# 05_Ethernet_Interface.net
KiCad netlist of a schematic drawn in Altium Designer
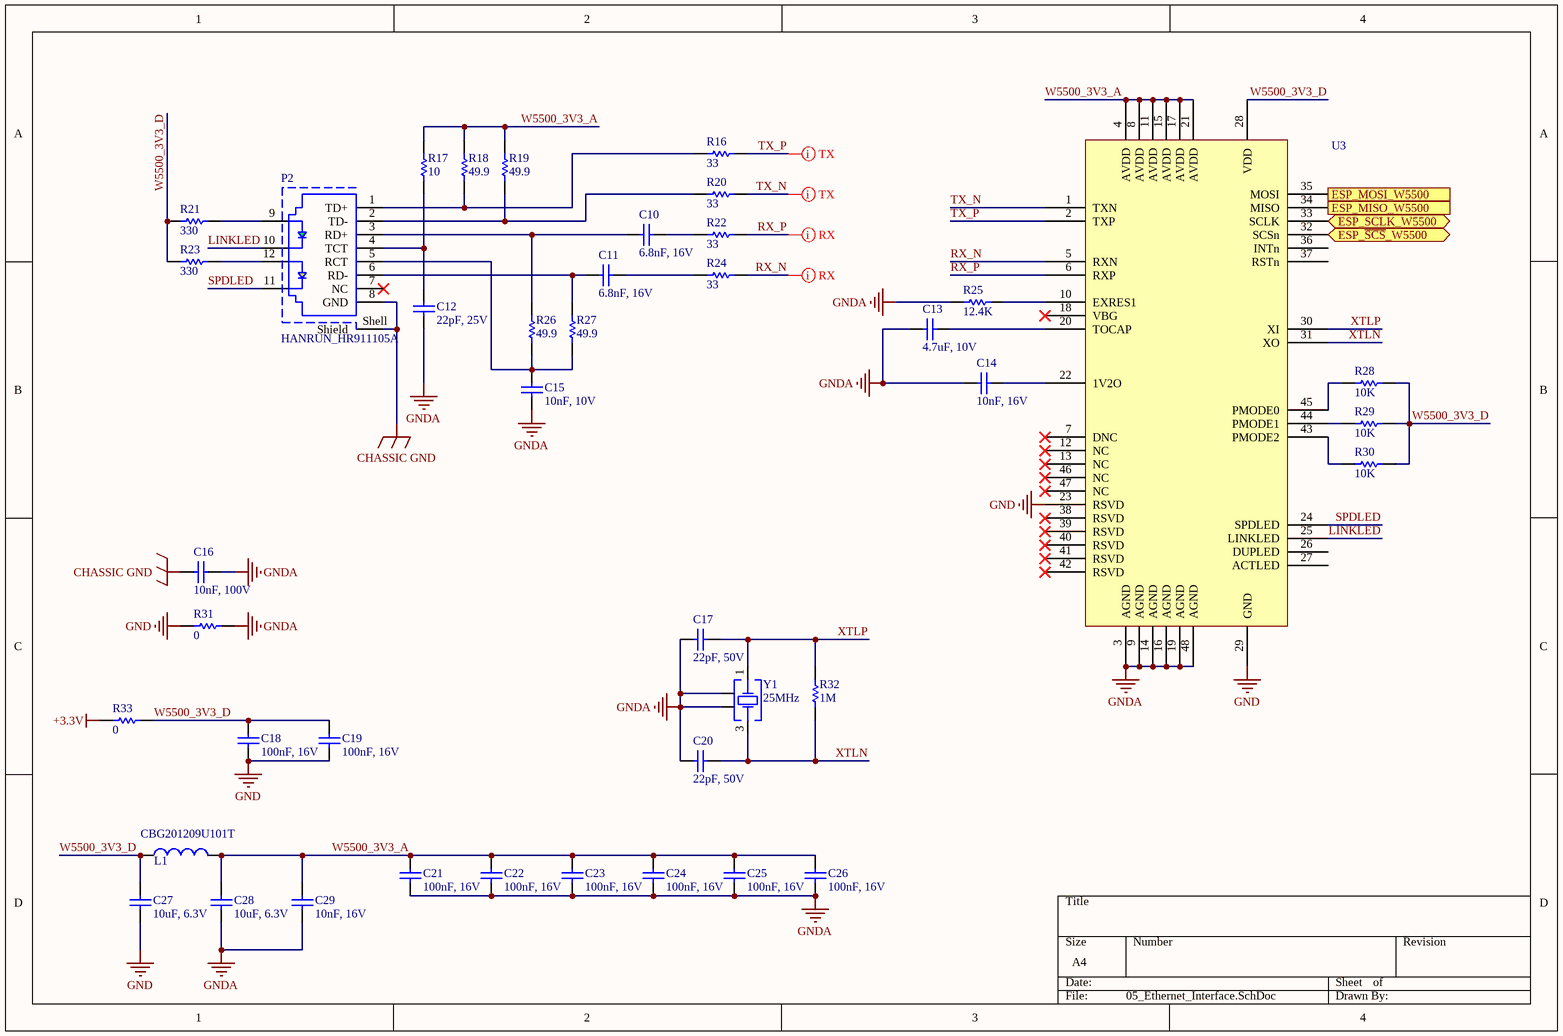
[diagram p0: 05_Ethernet_Interface.SchDoc]

(export (version "E")
  (design (tool "Eeschema 10.0.6"))
  (components
    (comp (ref "C10")
      (value "6.8nF, 16V")
      (footprint "WCAP-CSGP_0603_H=0.8mm_Reflow")
      (description "WCAP-CSGP Multilayer Ceramic Chip Capacitor, General Purpose, size 0603, X7R, 6.8nF, 16V")
      (fields
        (field (name "MANUFACTURER PART NUMBER") "885012206039")
        (field (name "MANUFACTURER") "Wurth Elektronik")
      )
      (libsource (lib "Altium_WCAP-CSGP (rev20a)") (part "885012206039"))
    )
    (comp (ref "C11")
      (value "6.8nF, 16V")
      (footprint "WCAP-CSGP_0603_H=0.8mm_Reflow")
      (description "WCAP-CSGP Multilayer Ceramic Chip Capacitor, General Purpose, size 0603, X7R, 6.8nF, 16V")
      (fields
        (field (name "MANUFACTURER PART NUMBER") "885012206039")
        (field (name "MANUFACTURER") "Wurth Elektronik")
      )
      (libsource (lib "Altium_WCAP-CSGP (rev20a)") (part "885012206039"))
    )
    (comp (ref "C12")
      (value "22pF, 25V")
      (footprint "WCAP-CSGP_0603_H=0.8mm_Reflow")
      (description "WCAP-CSGP Multilayer Ceramic Chip Capacitor, General Purpose, size 0603, NP0, 22pF, 25V")
      (fields
        (field (name "MANUFACTURER PART NUMBER") "885012006034")
        (field (name "MANUFACTURER") "Wurth Elektronik")
      )
      (libsource (lib "Altium_WCAP-CSGP (rev20a)") (part "885012006034"))
    )
    (comp (ref "C13")
      (value "4.7uF, 10V")
      (footprint "WCAP-CSGP_0603_H=0.8mm_Reflow")
      (description "WCAP-CSGP Multilayer Ceramic Chip Capacitor, General Purpose, size 0603, X5R, 4.7uF, 10V")
      (fields
        (field (name "MANUFACTURER PART NUMBER") "885012106012")
        (field (name "MANUFACTURER") "Wurth Elektronik")
      )
      (libsource (lib "Altium_WCAP-CSGP (rev20a)") (part "885012106012"))
    )
    (comp (ref "C14")
      (value "10nF, 16V")
      (footprint "WCAP-CSGP_0603_H=0.8mm_Reflow")
      (description "WCAP-CSGP Multilayer Ceramic Chip Capacitor, General Purpose, size 0603, X7R, 10nF, 16V")
      (fields
        (field (name "MANUFACTURER PART NUMBER") "885012206040")
        (field (name "MANUFACTURER") "Wurth Elektronik")
      )
      (libsource (lib "Altium_WCAP-CSGP (rev20a)") (part "885012206040"))
    )
    (comp (ref "C15")
      (value "10nF, 10V")
      (footprint "WCAP-CSGP_0603_H=0.8mm_Reflow")
      (description "WCAP-CSGP Multilayer Ceramic Chip Capacitor, General Purpose, size 0603, X7R, 10nF, 10V")
      (fields
        (field (name "MANUFACTURER PART NUMBER") "885012206014")
        (field (name "MANUFACTURER") "Wurth Elektronik")
      )
      (libsource (lib "Altium_WCAP-CSGP (rev20a)") (part "885012206014"))
    )
    (comp (ref "C16")
      (value "10nF, 100V")
      (footprint "WCAP-CSGP_0603_H=0.8mm_Reflow")
      (description "WCAP-CSGP Multilayer Ceramic Chip Capacitor, General Purpose, size 0603, X7R, 10nF, 100V")
      (fields
        (field (name "MANUFACTURER PART NUMBER") "885012206114")
        (field (name "MANUFACTURER") "Wurth Elektronik")
      )
      (libsource (lib "Altium_WCAP-CSGP (rev20a)") (part "885012206114"))
    )
    (comp (ref "C17")
      (value "22pF, 50V")
      (footprint "WCAP-CSGP_0603_H=0.8mm_Reflow")
      (description "WCAP-CSGP Multilayer Ceramic Chip Capacitor, General Purpose, size 0603, NP0, 22pF, 50V")
      (fields
        (field (name "MANUFACTURER PART NUMBER") "885012006053")
        (field (name "MANUFACTURER") "Wurth Elektronik")
      )
      (libsource (lib "Altium_WCAP-CSGP (rev20a)") (part "885012006053"))
    )
    (comp (ref "C18")
      (value "100nF, 16V")
      (footprint "WCAP-CSGP_0603_H=0.8mm_Reflow")
      (description "WCAP-CSGP Multilayer Ceramic Chip Capacitor, General Purpose, size 0603, X7R, 100nF, 16V")
      (fields
        (field (name "MANUFACTURER PART NUMBER") "885012206046")
        (field (name "MANUFACTURER") "Wurth Elektronik")
      )
      (libsource (lib "Altium_WCAP-CSGP (rev20a)") (part "885012206046"))
    )
    (comp (ref "C19")
      (value "100nF, 16V")
      (footprint "WCAP-CSGP_0603_H=0.8mm_Reflow")
      (description "WCAP-CSGP Multilayer Ceramic Chip Capacitor, General Purpose, size 0603, X7R, 100nF, 16V")
      (fields
        (field (name "MANUFACTURER PART NUMBER") "885012206046")
        (field (name "MANUFACTURER") "Wurth Elektronik")
      )
      (libsource (lib "Altium_WCAP-CSGP (rev20a)") (part "885012206046"))
    )
    (comp (ref "C20")
      (value "22pF, 50V")
      (footprint "WCAP-CSGP_0603_H=0.8mm_Reflow")
      (description "WCAP-CSGP Multilayer Ceramic Chip Capacitor, General Purpose, size 0603, NP0, 22pF, 50V")
      (fields
        (field (name "MANUFACTURER PART NUMBER") "885012006053")
        (field (name "MANUFACTURER") "Wurth Elektronik")
      )
      (libsource (lib "Altium_WCAP-CSGP (rev20a)") (part "885012006053"))
    )
    (comp (ref "C21")
      (value "100nF, 16V")
      (footprint "WCAP-CSGP_0603_H=0.8mm_Reflow")
      (description "WCAP-CSGP Multilayer Ceramic Chip Capacitor, General Purpose, size 0603, X7R, 100nF, 16V")
      (fields
        (field (name "MANUFACTURER PART NUMBER") "885012206046")
        (field (name "MANUFACTURER") "Wurth Elektronik")
      )
      (libsource (lib "Altium_WCAP-CSGP (rev20a)") (part "885012206046"))
    )
    (comp (ref "C22")
      (value "100nF, 16V")
      (footprint "WCAP-CSGP_0603_H=0.8mm_Reflow")
      (description "WCAP-CSGP Multilayer Ceramic Chip Capacitor, General Purpose, size 0603, X7R, 100nF, 16V")
      (fields
        (field (name "MANUFACTURER PART NUMBER") "885012206046")
        (field (name "MANUFACTURER") "Wurth Elektronik")
      )
      (libsource (lib "Altium_WCAP-CSGP (rev20a)") (part "885012206046"))
    )
    (comp (ref "C23")
      (value "100nF, 16V")
      (footprint "WCAP-CSGP_0603_H=0.8mm_Reflow")
      (description "WCAP-CSGP Multilayer Ceramic Chip Capacitor, General Purpose, size 0603, X7R, 100nF, 16V")
      (fields
        (field (name "MANUFACTURER PART NUMBER") "885012206046")
        (field (name "MANUFACTURER") "Wurth Elektronik")
      )
      (libsource (lib "Altium_WCAP-CSGP (rev20a)") (part "885012206046"))
    )
    (comp (ref "C24")
      (value "100nF, 16V")
      (footprint "WCAP-CSGP_0603_H=0.8mm_Reflow")
      (description "WCAP-CSGP Multilayer Ceramic Chip Capacitor, General Purpose, size 0603, X7R, 100nF, 16V")
      (fields
        (field (name "MANUFACTURER PART NUMBER") "885012206046")
        (field (name "MANUFACTURER") "Wurth Elektronik")
      )
      (libsource (lib "Altium_WCAP-CSGP (rev20a)") (part "885012206046"))
    )
    (comp (ref "C25")
      (value "100nF, 16V")
      (footprint "WCAP-CSGP_0603_H=0.8mm_Reflow")
      (description "WCAP-CSGP Multilayer Ceramic Chip Capacitor, General Purpose, size 0603, X7R, 100nF, 16V")
      (fields
        (field (name "MANUFACTURER PART NUMBER") "885012206046")
        (field (name "MANUFACTURER") "Wurth Elektronik")
      )
      (libsource (lib "Altium_WCAP-CSGP (rev20a)") (part "885012206046"))
    )
    (comp (ref "C26")
      (value "100nF, 16V")
      (footprint "WCAP-CSGP_0603_H=0.8mm_Reflow")
      (description "WCAP-CSGP Multilayer Ceramic Chip Capacitor, General Purpose, size 0603, X7R, 100nF, 16V")
      (fields
        (field (name "MANUFACTURER PART NUMBER") "885012206046")
        (field (name "MANUFACTURER") "Wurth Elektronik")
      )
      (libsource (lib "Altium_WCAP-CSGP (rev20a)") (part "885012206046"))
    )
    (comp (ref "C27")
      (value "10uF, 6.3V")
      (footprint "WCAP-CSGP_0603_H=0.8mm_Reflow")
      (description "WCAP-CSGP Multilayer Ceramic Chip Capacitor, General Purpose, size 0603, X5R, 10uF, 6.3V")
      (fields
        (field (name "MANUFACTURER PART NUMBER") "885012106006")
        (field (name "MANUFACTURER") "Wurth Elektronik")
      )
      (libsource (lib "Altium_WCAP-CSGP (rev20a)") (part "885012106006"))
    )
    (comp (ref "C28")
      (value "10uF, 6.3V")
      (footprint "WCAP-CSGP_0603_H=0.8mm_Reflow")
      (description "WCAP-CSGP Multilayer Ceramic Chip Capacitor, General Purpose, size 0603, X5R, 10uF, 6.3V")
      (fields
        (field (name "MANUFACTURER PART NUMBER") "885012106006")
        (field (name "MANUFACTURER") "Wurth Elektronik")
      )
      (libsource (lib "Altium_WCAP-CSGP (rev20a)") (part "885012106006"))
    )
    (comp (ref "C29")
      (value "10nF, 16V")
      (footprint "WCAP-CSGP_0603_H=0.8mm_Reflow")
      (description "WCAP-CSGP Multilayer Ceramic Chip Capacitor, General Purpose, size 0603, X7R, 10nF, 16V")
      (fields
        (field (name "MANUFACTURER PART NUMBER") "885012206040")
        (field (name "MANUFACTURER") "Wurth Elektronik")
      )
      (libsource (lib "Altium_WCAP-CSGP (rev20a)") (part "885012206040"))
    )
    (comp (ref "L1")
      (value "CBG201209U101T")
      (footprint "I0805")
      (libsource (lib "MiclsLib") (part "CBG201209U101T"))
    )
    (comp (ref "P2")
      (value "HANRUN_HR911105A")
      (footprint "HANRUN_HR911105A")
      (libsource (lib "MiclsLib") (part "HANRUN_HR911105A"))
    )
    (comp (ref "R16")
      (value "33")
      (footprint "R0603")
      (fields (field (name "Comment") "Resistor"))
      (libsource (lib "MiclsLib") (part "Resistor"))
    )
    (comp (ref "R17")
      (value "10")
      (footprint "R0603")
      (fields (field (name "Comment") "Resistor"))
      (libsource (lib "MiclsLib") (part "Resistor"))
    )
    (comp (ref "R18")
      (value "49.9")
      (footprint "R0603")
      (fields (field (name "Comment") "Resistor"))
      (libsource (lib "MiclsLib") (part "Resistor"))
    )
    (comp (ref "R19")
      (value "49.9")
      (footprint "R0603")
      (fields (field (name "Comment") "Resistor"))
      (libsource (lib "MiclsLib") (part "Resistor"))
    )
    (comp (ref "R20")
      (value "33")
      (footprint "R0603")
      (fields (field (name "Comment") "Resistor"))
      (libsource (lib "MiclsLib") (part "Resistor"))
    )
    (comp (ref "R21")
      (value "330")
      (footprint "R0603")
      (fields (field (name "Comment") "Resistor"))
      (libsource (lib "MiclsLib") (part "Resistor"))
    )
    (comp (ref "R22")
      (value "33")
      (footprint "R0603")
      (fields (field (name "Comment") "Resistor"))
      (libsource (lib "MiclsLib") (part "Resistor"))
    )
    (comp (ref "R23")
      (value "330")
      (footprint "R0603")
      (fields (field (name "Comment") "Resistor"))
      (libsource (lib "MiclsLib") (part "Resistor"))
    )
    (comp (ref "R24")
      (value "33")
      (footprint "R0603")
      (fields (field (name "Comment") "Resistor"))
      (libsource (lib "MiclsLib") (part "Resistor"))
    )
    (comp (ref "R25")
      (value "12.4K")
      (footprint "R0603")
      (fields (field (name "Comment") "Resistor"))
      (libsource (lib "MiclsLib") (part "Resistor"))
    )
    (comp (ref "R26")
      (value "49.9")
      (footprint "R0603")
      (fields (field (name "Comment") "Resistor"))
      (libsource (lib "MiclsLib") (part "Resistor"))
    )
    (comp (ref "R27")
      (value "49.9")
      (footprint "R0603")
      (fields (field (name "Comment") "Resistor"))
      (libsource (lib "MiclsLib") (part "Resistor"))
    )
    (comp (ref "R28")
      (value "10K")
      (footprint "R0603")
      (fields (field (name "Comment") "Resistor"))
      (libsource (lib "MiclsLib") (part "Resistor"))
    )
    (comp (ref "R29")
      (value "10K")
      (footprint "R0603")
      (fields (field (name "Comment") "Resistor"))
      (libsource (lib "MiclsLib") (part "Resistor"))
    )
    (comp (ref "R30")
      (value "10K")
      (footprint "R0603")
      (fields (field (name "Comment") "Resistor"))
      (libsource (lib "MiclsLib") (part "Resistor"))
    )
    (comp (ref "R31")
      (value "0")
      (footprint "R0603")
      (fields (field (name "Comment") "Resistor"))
      (libsource (lib "MiclsLib") (part "Resistor"))
    )
    (comp (ref "R32")
      (value "1M")
      (footprint "R0603")
      (fields (field (name "Comment") "Resistor"))
      (libsource (lib "MiclsLib") (part "Resistor"))
    )
    (comp (ref "R33")
      (value "0")
      (footprint "R0805")
      (fields (field (name "Comment") "Resistor"))
      (libsource (lib "MiclsLib") (part "Resistor"))
    )
    (comp (ref "U3")
      (value "W5500")
      (footprint "TSQFP50P900X900X160-48N")
      (libsource (lib "MiclsLib") (part "W5500"))
    )
    (comp (ref "Y1")
      (value "25MHz")
      (footprint "WE-XTAL_CFPX-180")
      (description "WE-XTAL Quartz Crystal, SMT, CFPX-180, 25MHz, +/-20ppm")
      (fields
        (field (name "MANUFACTURER PART NUMBER") "830108340809")
        (field (name "MANUFACTURER") "Wurth Elektronik")
      )
      (libsource (lib "Altium_WE-XTAL (rev20c)") (part "830108340809"))
    )
  )
  (nets
    (net (code "1") (name "+3.3V") (class "Default")
      (node (ref "R33") (pin "2") (pinfunction "2_2") (pintype "passive"))
    )
    (net (code "2") (name "/ESP_MISO_W5500") (class "Default")
      (node (ref "U3") (pin "34") (pinfunction "MISO_34") (pintype "passive"))
    )
    (net (code "3") (name "/ESP_MOSI_W5500") (class "Default")
      (node (ref "U3") (pin "35") (pinfunction "MOSI_35") (pintype "passive"))
    )
    (net (code "4") (name "/ESP_SCLK_W5500") (class "Default")
      (node (ref "U3") (pin "33") (pinfunction "SCLK_33") (pintype "passive"))
    )
    (net (code "5") (name "/ESP_~{SCS}_W5500") (class "Default")
      (node (ref "U3") (pin "32") (pinfunction "SCSn_32") (pintype "passive"))
    )
    (net (code "6") (name "/LINKLED") (class "Default")
      (node (ref "P2") (pin "10") (pinfunction "10_10") (pintype "passive"))
      (node (ref "U3") (pin "25") (pinfunction "LINKLED_25") (pintype "passive"))
    )
    (net (code "7") (name "/RX_N") (class "Default")
      (node (ref "R24") (pin "1") (pinfunction "1_1") (pintype "passive"))
      (node (ref "U3") (pin "5") (pinfunction "RXN_5") (pintype "passive"))
    )
    (net (code "8") (name "/RX_P") (class "Default")
      (node (ref "R22") (pin "1") (pinfunction "1_1") (pintype "passive"))
      (node (ref "U3") (pin "6") (pinfunction "RXP_6") (pintype "passive"))
    )
    (net (code "9") (name "/SPDLED") (class "Default")
      (node (ref "P2") (pin "11") (pinfunction "11_11") (pintype "passive"))
      (node (ref "U3") (pin "24") (pinfunction "SPDLED_24") (pintype "passive"))
    )
    (net (code "10") (name "/TX_N") (class "Default")
      (node (ref "R20") (pin "1") (pinfunction "1_1") (pintype "passive"))
      (node (ref "U3") (pin "1") (pinfunction "TXN_1") (pintype "passive"))
    )
    (net (code "11") (name "/TX_P") (class "Default")
      (node (ref "R16") (pin "1") (pinfunction "1_1") (pintype "passive"))
      (node (ref "U3") (pin "2") (pinfunction "TXP_2") (pintype "passive"))
    )
    (net (code "12") (name "/W5500_3V3_A") (class "Default")
      (node (ref "C21") (pin "2") (pinfunction "2_2") (pintype "passive"))
      (node (ref "C22") (pin "2") (pinfunction "2_2") (pintype "passive"))
      (node (ref "C23") (pin "2") (pinfunction "2_2") (pintype "passive"))
      (node (ref "C24") (pin "2") (pinfunction "2_2") (pintype "passive"))
      (node (ref "C25") (pin "2") (pinfunction "2_2") (pintype "passive"))
      (node (ref "C26") (pin "2") (pinfunction "2_2") (pintype "passive"))
      (node (ref "C28") (pin "2") (pinfunction "2_2") (pintype "passive"))
      (node (ref "C29") (pin "2") (pinfunction "2_2") (pintype "passive"))
      (node (ref "L1") (pin "2") (pinfunction "2_2") (pintype "passive"))
      (node (ref "R17") (pin "2") (pinfunction "2_2") (pintype "passive"))
      (node (ref "R18") (pin "2") (pinfunction "2_2") (pintype "passive"))
      (node (ref "R19") (pin "2") (pinfunction "2_2") (pintype "passive"))
      (node (ref "U3") (pin "11") (pinfunction "AVDD_11") (pintype "passive"))
      (node (ref "U3") (pin "15") (pinfunction "AVDD_15") (pintype "passive"))
      (node (ref "U3") (pin "17") (pinfunction "AVDD_17") (pintype "passive"))
      (node (ref "U3") (pin "21") (pinfunction "AVDD_21") (pintype "passive"))
      (node (ref "U3") (pin "4") (pinfunction "AVDD_4") (pintype "passive"))
      (node (ref "U3") (pin "8") (pinfunction "AVDD_8") (pintype "passive"))
    )
    (net (code "13") (name "/W5500_3V3_D") (class "Default")
      (node (ref "C18") (pin "2") (pinfunction "2_2") (pintype "passive"))
      (node (ref "C19") (pin "2") (pinfunction "2_2") (pintype "passive"))
      (node (ref "C27") (pin "2") (pinfunction "2_2") (pintype "passive"))
      (node (ref "L1") (pin "1") (pinfunction "1_1") (pintype "passive"))
      (node (ref "R21") (pin "2") (pinfunction "2_2") (pintype "passive"))
      (node (ref "R23") (pin "2") (pinfunction "2_2") (pintype "passive"))
      (node (ref "R28") (pin "2") (pinfunction "2_2") (pintype "passive"))
      (node (ref "R29") (pin "2") (pinfunction "2_2") (pintype "passive"))
      (node (ref "R30") (pin "2") (pinfunction "2_2") (pintype "passive"))
      (node (ref "R33") (pin "1") (pinfunction "1_1") (pintype "passive"))
      (node (ref "U3") (pin "28") (pinfunction "VDD_28") (pintype "passive"))
    )
    (net (code "14") (name "/XTLN") (class "Default")
      (node (ref "C20") (pin "2") (pinfunction "2_2") (pintype "passive"))
      (node (ref "R32") (pin "1") (pinfunction "1_1") (pintype "passive"))
      (node (ref "U3") (pin "31") (pinfunction "XO_31") (pintype "passive"))
      (node (ref "Y1") (pin "3") (pinfunction "Crystal_3") (pintype "passive"))
    )
    (net (code "15") (name "/XTLP") (class "Default")
      (node (ref "C17") (pin "2") (pinfunction "2_2") (pintype "passive"))
      (node (ref "R32") (pin "2") (pinfunction "2_2") (pintype "passive"))
      (node (ref "U3") (pin "30") (pinfunction "XI_30") (pintype "passive"))
      (node (ref "Y1") (pin "1") (pinfunction "Crystal_1") (pintype "passive"))
    )
    (net (code "16") (name "CHASSIC GND") (class "Default")
      (node (ref "C16") (pin "1") (pinfunction "1_1") (pintype "passive"))
      (node (ref "P2") (pin "8") (pinfunction "GND_8") (pintype "passive"))
      (node (ref "P2") (pin "Shell") (pinfunction "Shield_Shell") (pintype "passive"))
    )
    (net (code "17") (name "GND") (class "Default")
      (node (ref "C18") (pin "1") (pinfunction "1_1") (pintype "passive"))
      (node (ref "C19") (pin "1") (pinfunction "1_1") (pintype "passive"))
      (node (ref "C27") (pin "1") (pinfunction "1_1") (pintype "passive"))
      (node (ref "R31") (pin "2") (pinfunction "2_2") (pintype "passive"))
      (node (ref "U3") (pin "23") (pinfunction "RSVD_23") (pintype "passive"))
      (node (ref "U3") (pin "29") (pinfunction "GND_29") (pintype "passive"))
    )
    (net (code "18") (name "GNDA") (class "Default")
      (node (ref "C12") (pin "1") (pinfunction "1_1") (pintype "passive"))
      (node (ref "C13") (pin "1") (pinfunction "1_1") (pintype "passive"))
      (node (ref "C14") (pin "2") (pinfunction "2_2") (pintype "passive"))
      (node (ref "C15") (pin "1") (pinfunction "1_1") (pintype "passive"))
      (node (ref "C16") (pin "2") (pinfunction "2_2") (pintype "passive"))
      (node (ref "C17") (pin "1") (pinfunction "1_1") (pintype "passive"))
      (node (ref "C20") (pin "1") (pinfunction "1_1") (pintype "passive"))
      (node (ref "C21") (pin "1") (pinfunction "1_1") (pintype "passive"))
      (node (ref "C22") (pin "1") (pinfunction "1_1") (pintype "passive"))
      (node (ref "C23") (pin "1") (pinfunction "1_1") (pintype "passive"))
      (node (ref "C24") (pin "1") (pinfunction "1_1") (pintype "passive"))
      (node (ref "C25") (pin "1") (pinfunction "1_1") (pintype "passive"))
      (node (ref "C26") (pin "1") (pinfunction "1_1") (pintype "passive"))
      (node (ref "C28") (pin "1") (pinfunction "1_1") (pintype "passive"))
      (node (ref "C29") (pin "1") (pinfunction "1_1") (pintype "passive"))
      (node (ref "R25") (pin "2") (pinfunction "2_2") (pintype "passive"))
      (node (ref "R31") (pin "1") (pinfunction "1_1") (pintype "passive"))
      (node (ref "U3") (pin "14") (pinfunction "AGND_14") (pintype "passive"))
      (node (ref "U3") (pin "16") (pinfunction "AGND_16") (pintype "passive"))
      (node (ref "U3") (pin "19") (pinfunction "AGND_19") (pintype "passive"))
      (node (ref "U3") (pin "3") (pinfunction "AGND_3") (pintype "passive"))
      (node (ref "U3") (pin "48") (pinfunction "AGND_48") (pintype "passive"))
      (node (ref "U3") (pin "9") (pinfunction "AGND_9") (pintype "passive"))
      (node (ref "Y1") (pin "2") (pinfunction "GND&Lid_2") (pintype "passive"))
      (node (ref "Y1") (pin "4") (pinfunction "GND&Lid_4") (pintype "passive"))
    )
    (net (code "19") (name "Net-(C10-Pad2)") (class "Default")
      (node (ref "C10") (pin "2") (pinfunction "2_2") (pintype "passive"))
      (node (ref "R22") (pin "2") (pinfunction "2_2") (pintype "passive"))
    )
    (net (code "20") (name "Net-(C11-Pad2)") (class "Default")
      (node (ref "C11") (pin "2") (pinfunction "2_2") (pintype "passive"))
      (node (ref "R24") (pin "2") (pinfunction "2_2") (pintype "passive"))
    )
    (net (code "21") (name "Net-(P2-Pad9)") (class "Default")
      (node (ref "P2") (pin "9") (pinfunction "9_9") (pintype "passive"))
      (node (ref "R21") (pin "1") (pinfunction "1_1") (pintype "passive"))
    )
    (net (code "22") (name "Net-(P2-Pad12)") (class "Default")
      (node (ref "P2") (pin "12") (pinfunction "12_12") (pintype "passive"))
      (node (ref "R23") (pin "1") (pinfunction "1_1") (pintype "passive"))
    )
    (net (code "23") (name "Net-(P2-RCT)") (class "Default")
      (node (ref "C15") (pin "2") (pinfunction "2_2") (pintype "passive"))
      (node (ref "P2") (pin "5") (pinfunction "RCT_5") (pintype "passive"))
      (node (ref "R26") (pin "2") (pinfunction "2_2") (pintype "passive"))
      (node (ref "R27") (pin "2") (pinfunction "2_2") (pintype "passive"))
    )
    (net (code "24") (name "Net-(P2-RD+)") (class "Default")
      (node (ref "C10") (pin "1") (pinfunction "1_1") (pintype "passive"))
      (node (ref "P2") (pin "3") (pinfunction "RD+_3") (pintype "passive"))
      (node (ref "R26") (pin "1") (pinfunction "1_1") (pintype "passive"))
    )
    (net (code "25") (name "Net-(P2-RD-)") (class "Default")
      (node (ref "C11") (pin "1") (pinfunction "1_1") (pintype "passive"))
      (node (ref "P2") (pin "6") (pinfunction "RD-_6") (pintype "passive"))
      (node (ref "R27") (pin "1") (pinfunction "1_1") (pintype "passive"))
    )
    (net (code "26") (name "Net-(P2-TCT)") (class "Default")
      (node (ref "C12") (pin "2") (pinfunction "2_2") (pintype "passive"))
      (node (ref "P2") (pin "4") (pinfunction "TCT_4") (pintype "passive"))
      (node (ref "R17") (pin "1") (pinfunction "1_1") (pintype "passive"))
    )
    (net (code "27") (name "Net-(P2-TD+)") (class "Default")
      (node (ref "P2") (pin "1") (pinfunction "TD+_1") (pintype "passive"))
      (node (ref "R16") (pin "2") (pinfunction "2_2") (pintype "passive"))
      (node (ref "R18") (pin "1") (pinfunction "1_1") (pintype "passive"))
    )
    (net (code "28") (name "Net-(P2-TD-)") (class "Default")
      (node (ref "P2") (pin "2") (pinfunction "TD-_2") (pintype "passive"))
      (node (ref "R19") (pin "1") (pinfunction "1_1") (pintype "passive"))
      (node (ref "R20") (pin "2") (pinfunction "2_2") (pintype "passive"))
    )
    (net (code "29") (name "Net-(U3-1V2O)") (class "Default")
      (node (ref "C14") (pin "1") (pinfunction "1_1") (pintype "passive"))
      (node (ref "U3") (pin "22") (pinfunction "1V2O_22") (pintype "passive"))
    )
    (net (code "30") (name "Net-(U3-EXRES1)") (class "Default")
      (node (ref "R25") (pin "1") (pinfunction "1_1") (pintype "passive"))
      (node (ref "U3") (pin "10") (pinfunction "EXRES1_10") (pintype "passive"))
    )
    (net (code "31") (name "Net-(U3-PMODE0)") (class "Default")
      (node (ref "R28") (pin "1") (pinfunction "1_1") (pintype "passive"))
      (node (ref "U3") (pin "45") (pinfunction "PMODE0_45") (pintype "passive"))
    )
    (net (code "32") (name "Net-(U3-PMODE1)") (class "Default")
      (node (ref "R29") (pin "1") (pinfunction "1_1") (pintype "passive"))
      (node (ref "U3") (pin "44") (pinfunction "PMODE1_44") (pintype "passive"))
    )
    (net (code "33") (name "Net-(U3-PMODE2)") (class "Default")
      (node (ref "R30") (pin "1") (pinfunction "1_1") (pintype "passive"))
      (node (ref "U3") (pin "43") (pinfunction "PMODE2_43") (pintype "passive"))
    )
    (net (code "34") (name "Net-(U3-TOCAP)") (class "Default")
      (node (ref "C13") (pin "2") (pinfunction "2_2") (pintype "passive"))
      (node (ref "U3") (pin "20") (pinfunction "TOCAP_20") (pintype "passive"))
    )
    (net (code "35") (name "unconnected-(P2-NC-Pad7)") (class "Default")
      (node (ref "P2") (pin "7") (pinfunction "NC_7") (pintype "passive+no_connect"))
    )
    (net (code "36") (name "unconnected-(U3-ACTLED-Pad27)") (class "Default")
      (node (ref "U3") (pin "27") (pinfunction "ACTLED_27") (pintype "passive"))
    )
    (net (code "37") (name "unconnected-(U3-DNC-Pad7)") (class "Default")
      (node (ref "U3") (pin "7") (pinfunction "DNC_7") (pintype "passive+no_connect"))
    )
    (net (code "38") (name "unconnected-(U3-DUPLED-Pad26)") (class "Default")
      (node (ref "U3") (pin "26") (pinfunction "DUPLED_26") (pintype "passive"))
    )
    (net (code "39") (name "unconnected-(U3-INTn-Pad36)") (class "Default")
      (node (ref "U3") (pin "36") (pinfunction "INTn_36") (pintype "passive"))
    )
    (net (code "40") (name "unconnected-(U3-NC-Pad12)") (class "Default")
      (node (ref "U3") (pin "12") (pinfunction "NC_12") (pintype "passive+no_connect"))
    )
    (net (code "41") (name "unconnected-(U3-NC-Pad13)") (class "Default")
      (node (ref "U3") (pin "13") (pinfunction "NC_13") (pintype "passive+no_connect"))
    )
    (net (code "42") (name "unconnected-(U3-NC-Pad46)") (class "Default")
      (node (ref "U3") (pin "46") (pinfunction "NC_46") (pintype "passive+no_connect"))
    )
    (net (code "43") (name "unconnected-(U3-NC-Pad47)") (class "Default")
      (node (ref "U3") (pin "47") (pinfunction "NC_47") (pintype "passive+no_connect"))
    )
    (net (code "44") (name "unconnected-(U3-RSTn-Pad37)") (class "Default")
      (node (ref "U3") (pin "37") (pinfunction "RSTn_37") (pintype "passive"))
    )
    (net (code "45") (name "unconnected-(U3-RSVD-Pad38)") (class "Default")
      (node (ref "U3") (pin "38") (pinfunction "RSVD_38") (pintype "passive+no_connect"))
    )
    (net (code "46") (name "unconnected-(U3-RSVD-Pad39)") (class "Default")
      (node (ref "U3") (pin "39") (pinfunction "RSVD_39") (pintype "passive+no_connect"))
    )
    (net (code "47") (name "unconnected-(U3-RSVD-Pad40)") (class "Default")
      (node (ref "U3") (pin "40") (pinfunction "RSVD_40") (pintype "passive+no_connect"))
    )
    (net (code "48") (name "unconnected-(U3-RSVD-Pad41)") (class "Default")
      (node (ref "U3") (pin "41") (pinfunction "RSVD_41") (pintype "passive+no_connect"))
    )
    (net (code "49") (name "unconnected-(U3-RSVD-Pad42)") (class "Default")
      (node (ref "U3") (pin "42") (pinfunction "RSVD_42") (pintype "passive+no_connect"))
    )
    (net (code "50") (name "unconnected-(U3-VBG-Pad18)") (class "Default")
      (node (ref "U3") (pin "18") (pinfunction "VBG_18") (pintype "passive+no_connect"))
    )
  )
)
